# WLAN.net
KiCad netlist of a schematic drawn in Altium Designer
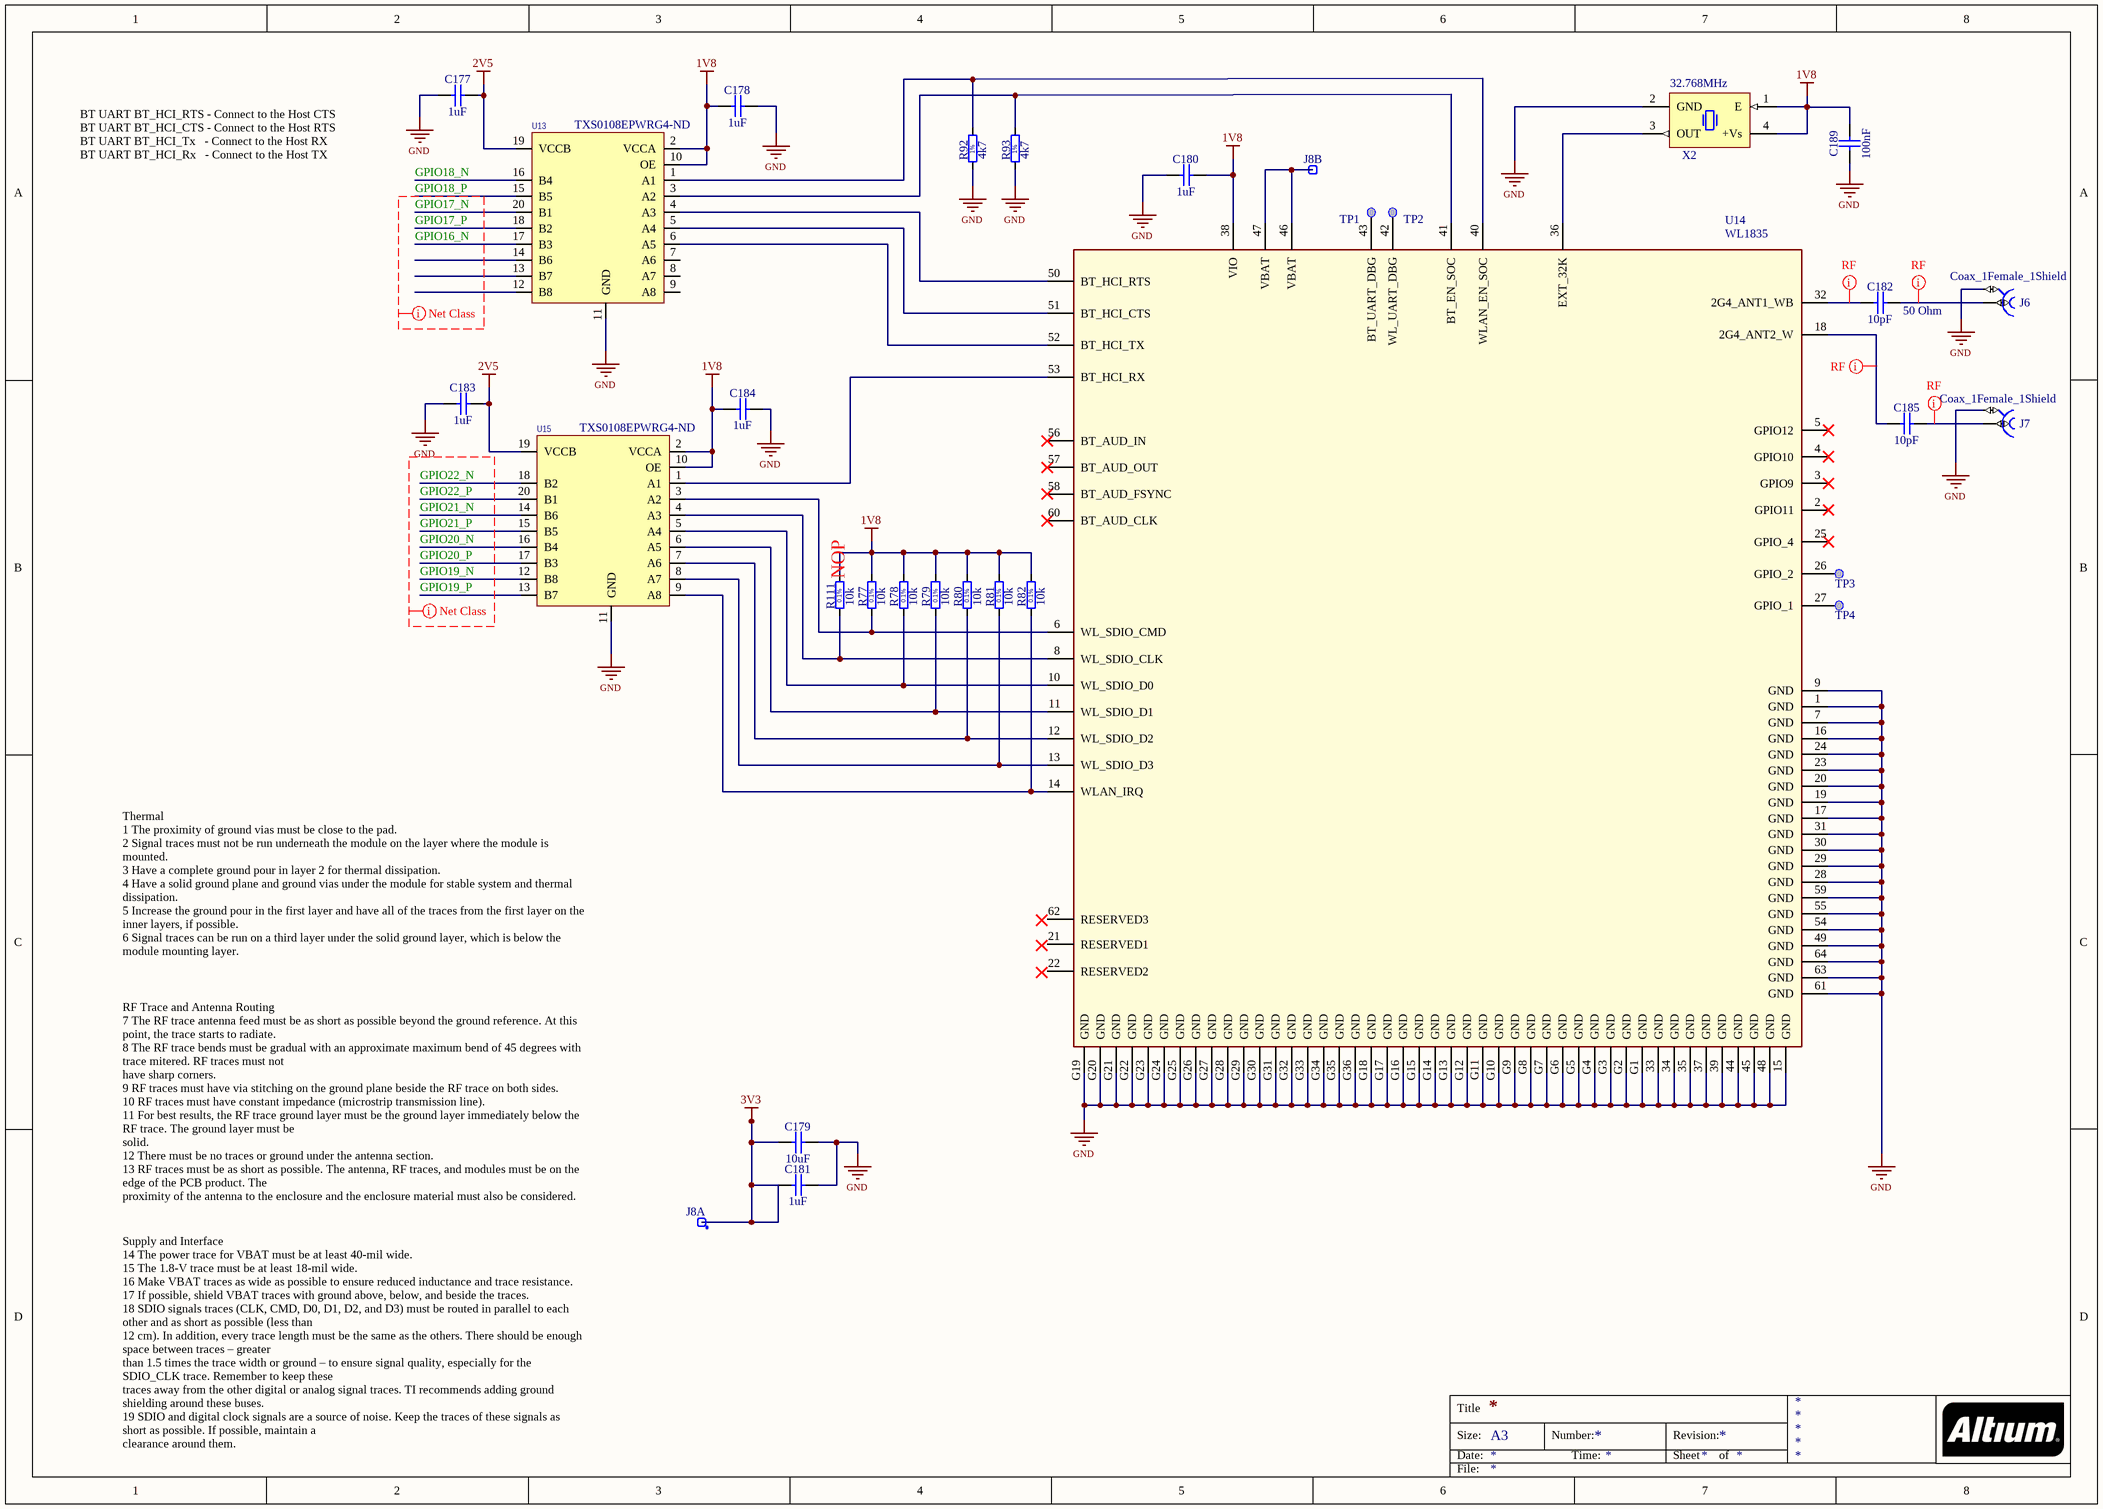
[diagram p0: WLAN.SchDoc]

(export (version "E")
  (design (tool "Eeschema 10.0.6"))
  (components
    (comp (ref "C177")
      (value "1uF")
      (footprint "CAPC1608X87N")
      (description "Non-polarised capacitor")
      (fields
        (field (name "PART NUMBER") "CC0603_1UF_25V_10%_X7R")
        (field (name "VOLTAGE") "25V")
        (field (name "AUTHOR") "CERN DEM JLC")
      )
      (libsource (lib "Capacitors") (part "Capacitor - non polarized"))
    )
    (comp (ref "C178")
      (value "1uF")
      (footprint "CAPC1608X87N")
      (description "Non-polarised capacitor")
      (fields
        (field (name "PART NUMBER") "CC0603_1UF_25V_10%_X7R")
        (field (name "VOLTAGE") "25V")
        (field (name "AUTHOR") "CERN DEM JLC")
      )
      (libsource (lib "Capacitors") (part "Capacitor - non polarized"))
    )
    (comp (ref "C179")
      (value "10uF")
      (footprint "CAPC2012X135N")
      (description "Non-polarised capacitor")
      (fields
        (field (name "PART NUMBER") "CC0805_10UF_10V_10%_X7R")
        (field (name "VOLTAGE") "10V")
        (field (name "AUTHOR") "CERN DEM JLC")
      )
      (libsource (lib "Capacitors") (part "Capacitor - non polarized"))
    )
    (comp (ref "C180")
      (value "1uF")
      (footprint "CAPC1608X87N")
      (description "Non-polarised capacitor")
      (fields
        (field (name "PART NUMBER") "CC0603_1UF_25V_10%_X7R")
        (field (name "VOLTAGE") "25V")
        (field (name "AUTHOR") "CERN DEM JLC")
      )
      (libsource (lib "Capacitors") (part "Capacitor - non polarized"))
    )
    (comp (ref "C181")
      (value "1uF")
      (footprint "CAPC1608X87N")
      (description "Non-polarised capacitor")
      (fields
        (field (name "PART NUMBER") "CC0603_1UF_25V_10%_X7R")
        (field (name "VOLTAGE") "25V")
        (field (name "AUTHOR") "CERN DEM JLC")
      )
      (libsource (lib "Capacitors") (part "Capacitor - non polarized"))
    )
    (comp (ref "C182")
      (value "10pF")
      (footprint "CAPC1608X87N")
      (description "Non-polarised capacitor")
      (fields
        (field (name "PART NUMBER") "CC0603_10PF_50V_5%_NP0")
        (field (name "VOLTAGE") "50V")
        (field (name "AUTHOR") "CERN DEM JLC")
      )
      (libsource (lib "Capacitors") (part "Capacitor - non polarized"))
    )
    (comp (ref "C183")
      (value "1uF")
      (footprint "CAPC1608X87N")
      (description "Non-polarised capacitor")
      (fields
        (field (name "PART NUMBER") "CC0603_1UF_25V_10%_X7R")
        (field (name "VOLTAGE") "25V")
        (field (name "AUTHOR") "CERN DEM JLC")
      )
      (libsource (lib "Capacitors") (part "Capacitor - non polarized"))
    )
    (comp (ref "C184")
      (value "1uF")
      (footprint "CAPC1608X87N")
      (description "Non-polarised capacitor")
      (fields
        (field (name "PART NUMBER") "CC0603_1UF_25V_10%_X7R")
        (field (name "VOLTAGE") "25V")
        (field (name "AUTHOR") "CERN DEM JLC")
      )
      (libsource (lib "Capacitors") (part "Capacitor - non polarized"))
    )
    (comp (ref "C185")
      (value "10pF")
      (footprint "CAPC1608X87N")
      (description "Non-polarised capacitor")
      (fields
        (field (name "PART NUMBER") "CC0603_10PF_50V_5%_NP0")
        (field (name "VOLTAGE") "50V")
        (field (name "AUTHOR") "CERN DEM JLC")
      )
      (libsource (lib "Capacitors") (part "Capacitor - non polarized"))
    )
    (comp (ref "C189")
      (value "100nF")
      (footprint "CAPC1608X87N")
      (description "Non-polarised capacitor")
      (fields
        (field (name "PART NUMBER") "CC0603_100NF_50V_10%_X7R")
        (field (name "VOLTAGE") "50V")
        (field (name "AUTHOR") "CERN DEM JLC")
      )
      (libsource (lib "") (part "Capacitor - non polarized_1"))
    )
    (comp (ref "J6")
      (value "Coax_1Female_1Shield")
      (footprint "HUBER-SUHNER_82 SMA-50-0-41/133 NE")
      (fields
        (field (name "PART NUMBER") "HUBER-SUHNER_82_SMA-50-0-41/133_NE")
        (field (name "MANUFACTURER") "AMPHENOL CONNEX")
        (field (name "MANUFACTURER PART NUMBER") "132134")
        (field (name "AUTHOR") "CERN DEM JLC")
      )
      (libsource (lib "Connectors") (part "Coax_1Female_1Shield"))
    )
    (comp (ref "J7")
      (value "Coax_1Female_1Shield")
      (footprint "HUBER-SUHNER_82 SMA-50-0-41/133 NE")
      (fields
        (field (name "PART NUMBER") "HUBER-SUHNER_82_SMA-50-0-41/133_NE")
        (field (name "MANUFACTURER") "AMPHENOL CONNEX")
        (field (name "MANUFACTURER PART NUMBER") "132134")
        (field (name "AUTHOR") "CERN DEM JLC")
      )
      (libsource (lib "Connectors") (part "Coax_1Female_1Shield"))
    )
    (comp (ref "J8")
      (value "Test Point")
      (footprint "COMATEL_385.0358.1.02.400")
      (description "2 Mini Wire-Wrap Contact Strip Header")
      (fields
        (field (name "PART NUMBER") "COMATEL_385.0358.1.02.400")
        (field (name "MANUFACTURER") "KONTEK COMATEL")
        (field (name "AUTHOR") "CERN DEM JLC")
      )
      (libsource (lib "Connectors") (part "Wire-Wrap Contact x2"))
    )
    (comp (ref "R77")
      (value "10k")
      (footprint "RESC1608X55N")
      (description "Resistor - 0.1%")
      (fields
        (field (name "PART NUMBER") "R0603_10K_0.1%_0.063W_10PPM")
        (field (name "POWER") "0.063W")
        (field (name "AUTHOR") "CERN DEM JLC")
      )
      (libsource (lib "Resistors") (part "Resistor - 0.1%"))
    )
    (comp (ref "R78")
      (value "10k")
      (footprint "RESC1608X55N")
      (description "Resistor - 0.1%")
      (fields
        (field (name "PART NUMBER") "R0603_10K_0.1%_0.063W_10PPM")
        (field (name "POWER") "0.063W")
        (field (name "AUTHOR") "CERN DEM JLC")
      )
      (libsource (lib "Resistors") (part "Resistor - 0.1%"))
    )
    (comp (ref "R79")
      (value "10k")
      (footprint "RESC1608X55N")
      (description "Resistor - 0.1%")
      (fields
        (field (name "PART NUMBER") "R0603_10K_0.1%_0.063W_10PPM")
        (field (name "POWER") "0.063W")
        (field (name "AUTHOR") "CERN DEM JLC")
      )
      (libsource (lib "Resistors") (part "Resistor - 0.1%"))
    )
    (comp (ref "R80")
      (value "10k")
      (footprint "RESC1608X55N")
      (description "Resistor - 0.1%")
      (fields
        (field (name "PART NUMBER") "R0603_10K_0.1%_0.063W_10PPM")
        (field (name "POWER") "0.063W")
        (field (name "AUTHOR") "CERN DEM JLC")
      )
      (libsource (lib "Resistors") (part "Resistor - 0.1%"))
    )
    (comp (ref "R81")
      (value "10k")
      (footprint "RESC1608X55N")
      (description "Resistor - 0.1%")
      (fields
        (field (name "PART NUMBER") "R0603_10K_0.1%_0.063W_10PPM")
        (field (name "POWER") "0.063W")
        (field (name "AUTHOR") "CERN DEM JLC")
      )
      (libsource (lib "Resistors") (part "Resistor - 0.1%"))
    )
    (comp (ref "R82")
      (value "10k")
      (footprint "RESC1608X55N")
      (description "Resistor - 0.1%")
      (fields
        (field (name "PART NUMBER") "R0603_10K_0.1%_0.063W_10PPM")
        (field (name "POWER") "0.063W")
        (field (name "AUTHOR") "CERN DEM JLC")
      )
      (libsource (lib "Resistors") (part "Resistor - 0.1%"))
    )
    (comp (ref "R92")
      (value "4k7")
      (footprint "RESC1608X55N")
      (description "Resistor - 1%")
      (fields
        (field (name "PART NUMBER") "R0603_4K7_1%_0.1W_100PPM")
        (field (name "POWER") "0.1W")
        (field (name "AUTHOR") "CERN DEM JLC")
      )
      (libsource (lib "Resistors") (part "Resistor - 1%"))
    )
    (comp (ref "R93")
      (value "4k7")
      (footprint "RESC1608X55N")
      (description "Resistor - 1%")
      (fields
        (field (name "PART NUMBER") "R0603_4K7_1%_0.1W_100PPM")
        (field (name "POWER") "0.1W")
        (field (name "AUTHOR") "CERN DEM JLC")
      )
      (libsource (lib "Resistors") (part "Resistor - 1%"))
    )
    (comp (ref "R111")
      (value "10k")
      (footprint "RESC1608X55N")
      (description "Resistor - 0.1%")
      (fields
        (field (name "PART NUMBER") "R0603_10K_0.1%_0.063W_10PPM")
        (field (name "POWER") "0.063W")
        (field (name "AUTHOR") "CERN DEM JLC")
      )
      (libsource (lib "Resistors") (part "Resistor - 0.1%"))
    )
    (comp (ref "TP1")
      (value "TP")
      (footprint "TP")
      (description "Test Point")
      (libsource (lib "SCHLIB") (part "Test Point"))
    )
    (comp (ref "TP2")
      (value "TP")
      (footprint "TP")
      (description "Test Point")
      (libsource (lib "SCHLIB") (part "Test Point"))
    )
    (comp (ref "TP3")
      (value "TP")
      (footprint "TP")
      (description "Test Point")
      (libsource (lib "SCHLIB") (part "Test Point"))
    )
    (comp (ref "TP4")
      (value "TP")
      (footprint "TP")
      (description "Test Point")
      (libsource (lib "SCHLIB") (part "Test Point"))
    )
    (comp (ref "U13")
      (value "TXS0108EPWR")
      (footprint "SOP65P640X120-20N")
      (description "IC 8BIT NON-INV TRANSLTR 20TSSOP")
      (fields
        (field (name "MANUFACTURER PART NUMBER") "TXS0108EPWRG4")
        (field (name "MANUFACTURER") "Texas Instruments")
        (field (name "SUPPLIER PART NUMBER") "TXS0108EPWRG4-ND")
      )
      (libsource (lib "SCHLIB") (part "TXS0108EPWR"))
    )
    (comp (ref "U14")
      (value "WL1835")
      (footprint "E-13.4X13.3-N100_0.75-TOP")
      (description "MODULE WIFI WILINK")
      (fields
        (field (name "MANUFACTURER PART NUMBER") "WL1835MODGBMOCR")
        (field (name "MANUFACTURER") "Texas Instruments")
      )
      (libsource (lib "SCHLIB") (part "WL1835"))
    )
    (comp (ref "U15")
      (value "TXS0108EPWR")
      (footprint "SOP65P640X120-20N")
      (description "IC 8BIT NON-INV TRANSLTR 20TSSOP")
      (fields
        (field (name "MANUFACTURER PART NUMBER") "TXS0108EPWRG4")
        (field (name "MANUFACTURER") "Texas Instruments")
        (field (name "SUPPLIER PART NUMBER") "TXS0108EPWRG4-ND")
      )
      (libsource (lib "") (part "TXS0108EPWR_1"))
    )
    (comp (ref "X2")
      (value "32.768MHz")
      (footprint "OSCSC508P500X700X180-4N")
      (description "Oscillator 4 pins 1=E 2=GND 3=OUT 4=+Vs")
      (fields
        (field (name "PART NUMBER") "OSC_32.7688MHZ_RAKON_LF SPXO019203")
        (field (name "MANUFACTURER") "EPSON")
        (field (name "AUTHOR") "CERN DEM JLC")
      )
      (libsource (lib "ICs And Semiconductors") (part "Oscillator 1E 2GND 3OUT 4Vs"))
    )
  )
  (nets
    (net (code "1") (name "/GPIO16_N") (class "Default")
      (node (ref "U13") (pin "17") (pinfunction "B3_17") (pintype "passive"))
    )
    (net (code "2") (name "/GPIO17_N") (class "Default")
      (node (ref "U13") (pin "20") (pinfunction "B1_20") (pintype "passive"))
    )
    (net (code "3") (name "/GPIO17_P") (class "Default")
      (node (ref "U13") (pin "18") (pinfunction "B2_18") (pintype "passive"))
    )
    (net (code "4") (name "/GPIO18_N") (class "Default")
      (node (ref "U13") (pin "16") (pinfunction "B4_16") (pintype "passive"))
    )
    (net (code "5") (name "/GPIO18_P") (class "Default")
      (node (ref "U13") (pin "15") (pinfunction "B5_15") (pintype "passive"))
    )
    (net (code "6") (name "/GPIO19_N") (class "Default")
      (node (ref "U15") (pin "12") (pinfunction "B8_12") (pintype "passive"))
    )
    (net (code "7") (name "/GPIO19_P") (class "Default")
      (node (ref "U15") (pin "13") (pinfunction "B7_13") (pintype "passive"))
    )
    (net (code "8") (name "/GPIO20_N") (class "Default")
      (node (ref "U15") (pin "16") (pinfunction "B4_16") (pintype "passive"))
    )
    (net (code "9") (name "/GPIO20_P") (class "Default")
      (node (ref "U15") (pin "17") (pinfunction "B3_17") (pintype "passive"))
    )
    (net (code "10") (name "/GPIO21_N") (class "Default")
      (node (ref "U15") (pin "14") (pinfunction "B6_14") (pintype "passive"))
    )
    (net (code "11") (name "/GPIO21_P") (class "Default")
      (node (ref "U15") (pin "15") (pinfunction "B5_15") (pintype "passive"))
    )
    (net (code "12") (name "/GPIO22_N") (class "Default")
      (node (ref "U15") (pin "18") (pinfunction "B2_18") (pintype "passive"))
    )
    (net (code "13") (name "/GPIO22_P") (class "Default")
      (node (ref "U15") (pin "20") (pinfunction "B1_20") (pintype "passive"))
    )
    (net (code "14") (name "1V8") (class "Default")
      (node (ref "C178") (pin "1") (pinfunction "1_1") (pintype "passive"))
      (node (ref "C180") (pin "2") (pinfunction "2_2") (pintype "passive"))
      (node (ref "C184") (pin "1") (pinfunction "1_1") (pintype "passive"))
      (node (ref "C189") (pin "2") (pinfunction "2_2") (pintype "passive"))
      (node (ref "R111") (pin "2") (pinfunction "2_2") (pintype "passive"))
      (node (ref "R77") (pin "2") (pinfunction "2_2") (pintype "passive"))
      (node (ref "R78") (pin "2") (pinfunction "2_2") (pintype "passive"))
      (node (ref "R79") (pin "2") (pinfunction "2_2") (pintype "passive"))
      (node (ref "R80") (pin "2") (pinfunction "2_2") (pintype "passive"))
      (node (ref "R81") (pin "2") (pinfunction "2_2") (pintype "passive"))
      (node (ref "R82") (pin "2") (pinfunction "2_2") (pintype "passive"))
      (node (ref "U13") (pin "10") (pinfunction "OE_10") (pintype "passive"))
      (node (ref "U13") (pin "2") (pinfunction "VCCA_2") (pintype "passive"))
      (node (ref "U14") (pin "38") (pinfunction "VIO_38") (pintype "power_in"))
      (node (ref "U15") (pin "10") (pinfunction "OE_10") (pintype "passive"))
      (node (ref "U15") (pin "2") (pinfunction "VCCA_2") (pintype "passive"))
      (node (ref "X2") (pin "1") (pinfunction "E_1") (pintype "input"))
      (node (ref "X2") (pin "4") (pinfunction "+Vs_4") (pintype "power_in"))
    )
    (net (code "15") (name "2V5") (class "Default")
      (node (ref "C177") (pin "2") (pinfunction "2_2") (pintype "passive"))
      (node (ref "C183") (pin "2") (pinfunction "2_2") (pintype "passive"))
      (node (ref "U13") (pin "19") (pinfunction "VCCB_19") (pintype "passive"))
      (node (ref "U15") (pin "19") (pinfunction "VCCB_19") (pintype "passive"))
    )
    (net (code "16") (name "3V3") (class "Default")
      (node (ref "C179") (pin "1") (pinfunction "1_1") (pintype "passive"))
      (node (ref "C181") (pin "1") (pinfunction "1_1") (pintype "passive"))
      (node (ref "J8") (pin "1") (pinfunction "1_1") (pintype "bidirectional"))
    )
    (net (code "17") (name "GND") (class "Default")
      (node (ref "C177") (pin "1") (pinfunction "1_1") (pintype "passive"))
      (node (ref "C178") (pin "2") (pinfunction "2_2") (pintype "passive"))
      (node (ref "C179") (pin "2") (pinfunction "2_2") (pintype "passive"))
      (node (ref "C180") (pin "1") (pinfunction "1_1") (pintype "passive"))
      (node (ref "C181") (pin "2") (pinfunction "2_2") (pintype "passive"))
      (node (ref "C183") (pin "1") (pinfunction "1_1") (pintype "passive"))
      (node (ref "C184") (pin "2") (pinfunction "2_2") (pintype "passive"))
      (node (ref "C189") (pin "1") (pinfunction "1_1") (pintype "passive"))
      (node (ref "J6") (pin "2") (pinfunction "2_2") (pintype "bidirectional"))
      (node (ref "J7") (pin "2") (pinfunction "2_2") (pintype "bidirectional"))
      (node (ref "R92") (pin "1") (pinfunction "1_1") (pintype "passive"))
      (node (ref "R93") (pin "1") (pinfunction "1_1") (pintype "passive"))
      (node (ref "U13") (pin "11") (pinfunction "GND_11") (pintype "passive"))
      (node (ref "U14") (pin "1") (pinfunction "GND_1") (pintype "power_in"))
      (node (ref "U14") (pin "15") (pinfunction "GND_15") (pintype "power_in"))
      (node (ref "U14") (pin "16") (pinfunction "GND_16") (pintype "power_in"))
      (node (ref "U14") (pin "17") (pinfunction "GND_17") (pintype "power_in"))
      (node (ref "U14") (pin "19") (pinfunction "GND_19") (pintype "power_in"))
      (node (ref "U14") (pin "20") (pinfunction "GND_20") (pintype "power_in"))
      (node (ref "U14") (pin "23") (pinfunction "GND_23") (pintype "power_in"))
      (node (ref "U14") (pin "24") (pinfunction "GND_24") (pintype "power_in"))
      (node (ref "U14") (pin "28") (pinfunction "GND_28") (pintype "power_in"))
      (node (ref "U14") (pin "29") (pinfunction "GND_29") (pintype "power_in"))
      (node (ref "U14") (pin "30") (pinfunction "GND_30") (pintype "power_in"))
      (node (ref "U14") (pin "31") (pinfunction "GND_31") (pintype "power_in"))
      (node (ref "U14") (pin "33") (pinfunction "GND_33") (pintype "power_in"))
      (node (ref "U14") (pin "34") (pinfunction "GND_34") (pintype "power_in"))
      (node (ref "U14") (pin "35") (pinfunction "GND_35") (pintype "power_in"))
      (node (ref "U14") (pin "37") (pinfunction "GND_37") (pintype "power_in"))
      (node (ref "U14") (pin "39") (pinfunction "GND_39") (pintype "power_in"))
      (node (ref "U14") (pin "44") (pinfunction "GND_44") (pintype "power_in"))
      (node (ref "U14") (pin "45") (pinfunction "GND_45") (pintype "power_in"))
      (node (ref "U14") (pin "48") (pinfunction "GND_48") (pintype "power_in"))
      (node (ref "U14") (pin "49") (pinfunction "GND_49") (pintype "power_in"))
      (node (ref "U14") (pin "54") (pinfunction "GND_54") (pintype "power_in"))
      (node (ref "U14") (pin "55") (pinfunction "GND_55") (pintype "power_in"))
      (node (ref "U14") (pin "59") (pinfunction "GND_59") (pintype "power_in"))
      (node (ref "U14") (pin "61") (pinfunction "GND_61") (pintype "power_in"))
      (node (ref "U14") (pin "63") (pinfunction "GND_63") (pintype "power_in"))
      (node (ref "U14") (pin "64") (pinfunction "GND_64") (pintype "power_in"))
      (node (ref "U14") (pin "7") (pinfunction "GND_7") (pintype "power_in"))
      (node (ref "U14") (pin "9") (pinfunction "GND_9") (pintype "power_in"))
      (node (ref "U14") (pin "G1") (pinfunction "GND_G1") (pintype "power_in"))
      (node (ref "U14") (pin "G10") (pinfunction "GND_G10") (pintype "power_in"))
      (node (ref "U14") (pin "G11") (pinfunction "GND_G11") (pintype "power_in"))
      (node (ref "U14") (pin "G12") (pinfunction "GND_G12") (pintype "power_in"))
      (node (ref "U14") (pin "G13") (pinfunction "GND_G13") (pintype "power_in"))
      (node (ref "U14") (pin "G14") (pinfunction "GND_G14") (pintype "power_in"))
      (node (ref "U14") (pin "G15") (pinfunction "GND_G15") (pintype "power_in"))
      (node (ref "U14") (pin "G16") (pinfunction "GND_G16") (pintype "power_in"))
      (node (ref "U14") (pin "G17") (pinfunction "GND_G17") (pintype "power_in"))
      (node (ref "U14") (pin "G18") (pinfunction "GND_G18") (pintype "power_in"))
      (node (ref "U14") (pin "G19") (pinfunction "GND_G19") (pintype "power_in"))
      (node (ref "U14") (pin "G2") (pinfunction "GND_G2") (pintype "power_in"))
      (node (ref "U14") (pin "G20") (pinfunction "GND_G20") (pintype "power_in"))
      (node (ref "U14") (pin "G21") (pinfunction "GND_G21") (pintype "power_in"))
      (node (ref "U14") (pin "G22") (pinfunction "GND_G22") (pintype "power_in"))
      (node (ref "U14") (pin "G23") (pinfunction "GND_G23") (pintype "power_in"))
      (node (ref "U14") (pin "G24") (pinfunction "GND_G24") (pintype "power_in"))
      (node (ref "U14") (pin "G25") (pinfunction "GND_G25") (pintype "power_in"))
      (node (ref "U14") (pin "G26") (pinfunction "GND_G26") (pintype "power_in"))
      (node (ref "U14") (pin "G27") (pinfunction "GND_G27") (pintype "power_in"))
      (node (ref "U14") (pin "G28") (pinfunction "GND_G28") (pintype "power_in"))
      (node (ref "U14") (pin "G29") (pinfunction "GND_G29") (pintype "power_in"))
      (node (ref "U14") (pin "G3") (pinfunction "GND_G3") (pintype "power_in"))
      (node (ref "U14") (pin "G30") (pinfunction "GND_G30") (pintype "power_in"))
      (node (ref "U14") (pin "G31") (pinfunction "GND_G31") (pintype "power_in"))
      (node (ref "U14") (pin "G32") (pinfunction "GND_G32") (pintype "power_in"))
      (node (ref "U14") (pin "G33") (pinfunction "GND_G33") (pintype "power_in"))
      (node (ref "U14") (pin "G34") (pinfunction "GND_G34") (pintype "power_in"))
      (node (ref "U14") (pin "G35") (pinfunction "GND_G35") (pintype "power_in"))
      (node (ref "U14") (pin "G36") (pinfunction "GND_G36") (pintype "power_in"))
      (node (ref "U14") (pin "G4") (pinfunction "GND_G4") (pintype "power_in"))
      (node (ref "U14") (pin "G5") (pinfunction "GND_G5") (pintype "power_in"))
      (node (ref "U14") (pin "G6") (pinfunction "GND_G6") (pintype "power_in"))
      (node (ref "U14") (pin "G7") (pinfunction "GND_G7") (pintype "power_in"))
      (node (ref "U14") (pin "G8") (pinfunction "GND_G8") (pintype "power_in"))
      (node (ref "U14") (pin "G9") (pinfunction "GND_G9") (pintype "power_in"))
      (node (ref "U15") (pin "11") (pinfunction "GND_11") (pintype "passive"))
      (node (ref "X2") (pin "2") (pinfunction "GND_2") (pintype "power_in"))
    )
    (net (code "18") (name "Net-(C182-Pad2)") (class "Default")
      (node (ref "C182") (pin "2") (pinfunction "2_2") (pintype "passive"))
      (node (ref "J6") (pin "1") (pinfunction "1_1") (pintype "bidirectional"))
    )
    (net (code "19") (name "Net-(C185-Pad2)") (class "Default")
      (node (ref "C185") (pin "2") (pinfunction "2_2") (pintype "passive"))
      (node (ref "J7") (pin "1") (pinfunction "1_1") (pintype "bidirectional"))
    )
    (net (code "20") (name "Net-(J8-Pad2)") (class "Default")
      (node (ref "J8") (pin "2") (pinfunction "2_2") (pintype "bidirectional"))
      (node (ref "U14") (pin "46") (pinfunction "VBAT_46") (pintype "power_in"))
      (node (ref "U14") (pin "47") (pinfunction "VBAT_47") (pintype "power_in"))
    )
    (net (code "21") (name "Net-(U13-A1)") (class "Default")
      (node (ref "R92") (pin "2") (pinfunction "2_2") (pintype "passive"))
      (node (ref "U13") (pin "1") (pinfunction "A1_1") (pintype "passive"))
      (node (ref "U14") (pin "40") (pinfunction "WLAN_EN_SOC_40") (pintype "passive"))
    )
    (net (code "22") (name "Net-(U13-A2)") (class "Default")
      (node (ref "R93") (pin "2") (pinfunction "2_2") (pintype "passive"))
      (node (ref "U13") (pin "3") (pinfunction "A2_3") (pintype "passive"))
      (node (ref "U14") (pin "41") (pinfunction "BT_EN_SOC_41") (pintype "passive"))
    )
    (net (code "23") (name "Net-(U13-A3)") (class "Default")
      (node (ref "U13") (pin "4") (pinfunction "A3_4") (pintype "passive"))
      (node (ref "U14") (pin "50") (pinfunction "BT_HCI_RTS_50") (pintype "passive"))
    )
    (net (code "24") (name "Net-(U13-A4)") (class "Default")
      (node (ref "U13") (pin "5") (pinfunction "A4_5") (pintype "passive"))
      (node (ref "U14") (pin "51") (pinfunction "BT_HCI_CTS_51") (pintype "passive"))
    )
    (net (code "25") (name "Net-(U13-A5)") (class "Default")
      (node (ref "U13") (pin "6") (pinfunction "A5_6") (pintype "passive"))
      (node (ref "U14") (pin "52") (pinfunction "BT_HCI_TX_52") (pintype "passive"))
    )
    (net (code "26") (name "Net-(U14-2G4_ANT1_WB)") (class "Default")
      (node (ref "C182") (pin "1") (pinfunction "1_1") (pintype "passive"))
      (node (ref "U14") (pin "32") (pinfunction "2G4_ANT1_WB_32") (pintype "passive"))
    )
    (net (code "27") (name "Net-(U14-2G4_ANT2_W)") (class "Default")
      (node (ref "C185") (pin "1") (pinfunction "1_1") (pintype "passive"))
      (node (ref "U14") (pin "18") (pinfunction "2G4_ANT2_W_18") (pintype "passive"))
    )
    (net (code "28") (name "Net-(U14-BT_HCI_RX)") (class "Default")
      (node (ref "U14") (pin "53") (pinfunction "BT_HCI_RX_53") (pintype "passive"))
      (node (ref "U15") (pin "1") (pinfunction "A1_1") (pintype "passive"))
    )
    (net (code "29") (name "Net-(U14-BT_UART_DBG)") (class "Default")
      (node (ref "TP1") (pin "1") (pinfunction "1_1") (pintype "passive"))
      (node (ref "U14") (pin "43") (pinfunction "BT_UART_DBG_43") (pintype "passive"))
    )
    (net (code "30") (name "Net-(U14-EXT_32K)") (class "Default")
      (node (ref "U14") (pin "36") (pinfunction "EXT_32K_36") (pintype "passive"))
      (node (ref "X2") (pin "3") (pinfunction "OUT_3") (pintype "output"))
    )
    (net (code "31") (name "Net-(U14-GPIO_1)") (class "Default")
      (node (ref "TP4") (pin "1") (pinfunction "1_1") (pintype "passive"))
      (node (ref "U14") (pin "27") (pinfunction "GPIO_1_27") (pintype "passive"))
    )
    (net (code "32") (name "Net-(U14-GPIO_2)") (class "Default")
      (node (ref "TP3") (pin "1") (pinfunction "1_1") (pintype "passive"))
      (node (ref "U14") (pin "26") (pinfunction "GPIO_2_26") (pintype "passive"))
    )
    (net (code "33") (name "Net-(U14-WLAN_IRQ)") (class "Default")
      (node (ref "R82") (pin "1") (pinfunction "1_1") (pintype "passive"))
      (node (ref "U14") (pin "14") (pinfunction "WLAN_IRQ_14") (pintype "passive"))
      (node (ref "U15") (pin "9") (pinfunction "A8_9") (pintype "passive"))
    )
    (net (code "34") (name "Net-(U14-WL_SDIO_CLK)") (class "Default")
      (node (ref "R111") (pin "1") (pinfunction "1_1") (pintype "passive"))
      (node (ref "U14") (pin "8") (pinfunction "WL_SDIO_CLK_8") (pintype "passive"))
      (node (ref "U15") (pin "4") (pinfunction "A3_4") (pintype "passive"))
    )
    (net (code "35") (name "Net-(U14-WL_SDIO_CMD)") (class "Default")
      (node (ref "R77") (pin "1") (pinfunction "1_1") (pintype "passive"))
      (node (ref "U14") (pin "6") (pinfunction "WL_SDIO_CMD_6") (pintype "passive"))
      (node (ref "U15") (pin "3") (pinfunction "A2_3") (pintype "passive"))
    )
    (net (code "36") (name "Net-(U14-WL_SDIO_D0)") (class "Default")
      (node (ref "R78") (pin "1") (pinfunction "1_1") (pintype "passive"))
      (node (ref "U14") (pin "10") (pinfunction "WL_SDIO_D0_10") (pintype "passive"))
      (node (ref "U15") (pin "5") (pinfunction "A4_5") (pintype "passive"))
    )
    (net (code "37") (name "Net-(U14-WL_SDIO_D1)") (class "Default")
      (node (ref "R79") (pin "1") (pinfunction "1_1") (pintype "passive"))
      (node (ref "U14") (pin "11") (pinfunction "WL_SDIO_D1_11") (pintype "passive"))
      (node (ref "U15") (pin "6") (pinfunction "A5_6") (pintype "passive"))
    )
    (net (code "38") (name "Net-(U14-WL_SDIO_D2)") (class "Default")
      (node (ref "R80") (pin "1") (pinfunction "1_1") (pintype "passive"))
      (node (ref "U14") (pin "12") (pinfunction "WL_SDIO_D2_12") (pintype "passive"))
      (node (ref "U15") (pin "7") (pinfunction "A6_7") (pintype "passive"))
    )
    (net (code "39") (name "Net-(U14-WL_SDIO_D3)") (class "Default")
      (node (ref "R81") (pin "1") (pinfunction "1_1") (pintype "passive"))
      (node (ref "U14") (pin "13") (pinfunction "WL_SDIO_D3_13") (pintype "passive"))
      (node (ref "U15") (pin "8") (pinfunction "A7_8") (pintype "passive"))
    )
    (net (code "40") (name "Net-(U14-WL_UART_DBG)") (class "Default")
      (node (ref "TP2") (pin "1") (pinfunction "1_1") (pintype "passive"))
      (node (ref "U14") (pin "42") (pinfunction "WL_UART_DBG_42") (pintype "passive"))
    )
    (net (code "41") (name "unconnected-(U13-A6-Pad7)") (class "Default")
      (node (ref "U13") (pin "7") (pinfunction "A6_7") (pintype "passive"))
    )
    (net (code "42") (name "unconnected-(U13-A7-Pad8)") (class "Default")
      (node (ref "U13") (pin "8") (pinfunction "A7_8") (pintype "passive"))
    )
    (net (code "43") (name "unconnected-(U13-A8-Pad9)") (class "Default")
      (node (ref "U13") (pin "9") (pinfunction "A8_9") (pintype "passive"))
    )
    (net (code "44") (name "unconnected-(U13-B6-Pad14)") (class "Default")
      (node (ref "U13") (pin "14") (pinfunction "B6_14") (pintype "passive"))
    )
    (net (code "45") (name "unconnected-(U13-B7-Pad13)") (class "Default")
      (node (ref "U13") (pin "13") (pinfunction "B7_13") (pintype "passive"))
    )
    (net (code "46") (name "unconnected-(U13-B8-Pad12)") (class "Default")
      (node (ref "U13") (pin "12") (pinfunction "B8_12") (pintype "passive"))
    )
    (net (code "47") (name "unconnected-(U14-BT_AUD_CLK-Pad60)") (class "Default")
      (node (ref "U14") (pin "60") (pinfunction "BT_AUD_CLK_60") (pintype "passive+no_connect"))
    )
    (net (code "48") (name "unconnected-(U14-BT_AUD_FSYNC-Pad58)") (class "Default")
      (node (ref "U14") (pin "58") (pinfunction "BT_AUD_FSYNC_58") (pintype "passive+no_connect"))
    )
    (net (code "49") (name "unconnected-(U14-BT_AUD_IN-Pad56)") (class "Default")
      (node (ref "U14") (pin "56") (pinfunction "BT_AUD_IN_56") (pintype "passive+no_connect"))
    )
    (net (code "50") (name "unconnected-(U14-BT_AUD_OUT-Pad57)") (class "Default")
      (node (ref "U14") (pin "57") (pinfunction "BT_AUD_OUT_57") (pintype "passive+no_connect"))
    )
    (net (code "51") (name "unconnected-(U14-GPIO9-Pad3)") (class "Default")
      (node (ref "U14") (pin "3") (pinfunction "GPIO9_3") (pintype "passive+no_connect"))
    )
    (net (code "52") (name "unconnected-(U14-GPIO10-Pad4)") (class "Default")
      (node (ref "U14") (pin "4") (pinfunction "GPIO10_4") (pintype "passive+no_connect"))
    )
    (net (code "53") (name "unconnected-(U14-GPIO11-Pad2)") (class "Default")
      (node (ref "U14") (pin "2") (pinfunction "GPIO11_2") (pintype "passive+no_connect"))
    )
    (net (code "54") (name "unconnected-(U14-GPIO12-Pad5)") (class "Default")
      (node (ref "U14") (pin "5") (pinfunction "GPIO12_5") (pintype "passive+no_connect"))
    )
    (net (code "55") (name "unconnected-(U14-GPIO_4-Pad25)") (class "Default")
      (node (ref "U14") (pin "25") (pinfunction "GPIO_4_25") (pintype "passive+no_connect"))
    )
    (net (code "56") (name "unconnected-(U14-RESERVED1-Pad21)") (class "Default")
      (node (ref "U14") (pin "21") (pinfunction "RESERVED1_21") (pintype "passive"))
    )
    (net (code "57") (name "unconnected-(U14-RESERVED2-Pad22)") (class "Default")
      (node (ref "U14") (pin "22") (pinfunction "RESERVED2_22") (pintype "passive"))
    )
    (net (code "58") (name "unconnected-(U14-RESERVED3-Pad62)") (class "Default")
      (node (ref "U14") (pin "62") (pinfunction "RESERVED3_62") (pintype "passive"))
    )
  )
)
